# power_7V.net
KiCad netlist of a schematic drawn in Altium Designer
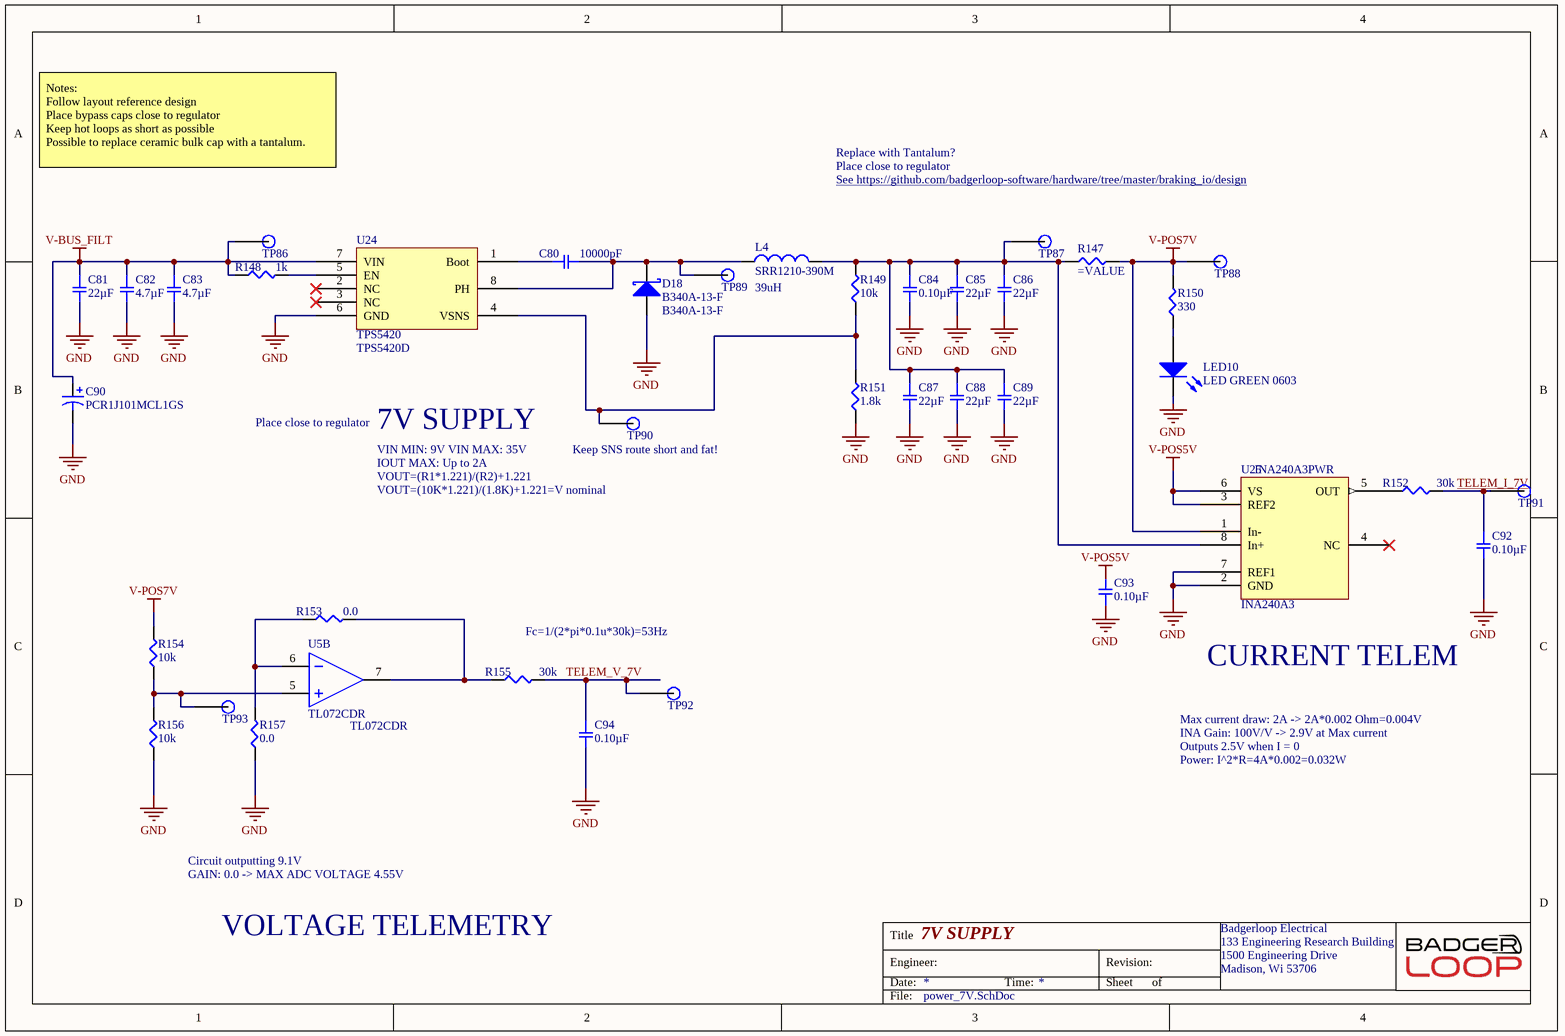
[diagram p0: power_7V.SchDoc]

(export (version "E")
  (design (tool "Eeschema 10.0.6"))
  (components
    (comp (ref "C80")
      (value "10000pF")
      (footprint "SMD-0805C")
      (description "CAP CER 10000PF 250V X7T 0805")
      (fields
        (field (name "DIGI-KEY PART NUMBER") "490-13986-1-ND")
        (field (name "PART NUMBER") "GC321AD72E103KX01D")
      )
      (libsource (lib "capacitors") (part "GC321AD72E103KX01D"))
    )
    (comp (ref "C81")
      (value "22µF")
      (footprint "SMD-1206C")
      (description "CAP CER 22UF 25V X5R 1206")
      (fields
        (field (name "DIGI-KEY PART NUMBER") "490-12451-1-ND")
        (field (name "PART NUMBER") "GRT31CR61E226ME01L")
      )
      (libsource (lib "capacitors") (part "GRT31CR61E226ME01L"))
    )
    (comp (ref "C82")
      (value "4.7µF")
      (footprint "SMD-1206C")
      (description "CAP CER 4.7UF 50V X7S 1206")
      (fields
        (field (name "DIGI-KEY PART NUMBER") "490-11167-1-ND")
        (field (name "PART NUMBER") "GCM31CC71H475KA03L")
      )
      (libsource (lib "capacitors") (part "GCM31CC71H475KA03L"))
    )
    (comp (ref "C83")
      (value "4.7µF")
      (footprint "SMD-1206C")
      (description "CAP CER 4.7UF 50V X7S 1206")
      (fields
        (field (name "DIGI-KEY PART NUMBER") "490-11167-1-ND")
        (field (name "PART NUMBER") "GCM31CC71H475KA03L")
      )
      (libsource (lib "capacitors") (part "GCM31CC71H475KA03L"))
    )
    (comp (ref "C84")
      (value "0.10µF")
      (footprint "SMD-0805C")
      (description "CAP CER 0.1UF 10V U2J 0805")
      (fields
        (field (name "DIGI-KEY PART NUMBER") "490-11592-1-ND")
        (field (name "PART NUMBER") "GRM21B7U1A104JA01L")
      )
      (libsource (lib "capacitors") (part "GRM21B7U1A104JA01L"))
    )
    (comp (ref "C85")
      (value "22µF")
      (footprint "SMD-1206C")
      (description "CAP CER 22UF 25V X5R 1206")
      (fields
        (field (name "DIGI-KEY PART NUMBER") "490-12451-1-ND")
        (field (name "PART NUMBER") "GRT31CR61E226ME01L")
      )
      (libsource (lib "capacitors") (part "GRT31CR61E226ME01L"))
    )
    (comp (ref "C86")
      (value "22µF")
      (footprint "SMD-1206C")
      (description "CAP CER 22UF 25V X5R 1206")
      (fields
        (field (name "DIGI-KEY PART NUMBER") "490-12451-1-ND")
        (field (name "PART NUMBER") "GRT31CR61E226ME01L")
      )
      (libsource (lib "capacitors") (part "GRT31CR61E226ME01L"))
    )
    (comp (ref "C87")
      (value "22µF")
      (footprint "SMD-1206C")
      (description "CAP CER 22UF 25V X5R 1206")
      (fields
        (field (name "DIGI-KEY PART NUMBER") "490-12451-1-ND")
        (field (name "PART NUMBER") "GRT31CR61E226ME01L")
      )
      (libsource (lib "capacitors") (part "GRT31CR61E226ME01L"))
    )
    (comp (ref "C88")
      (value "22µF")
      (footprint "SMD-1206C")
      (description "CAP CER 22UF 25V X5R 1206")
      (fields
        (field (name "DIGI-KEY PART NUMBER") "490-12451-1-ND")
        (field (name "PART NUMBER") "GRT31CR61E226ME01L")
      )
      (libsource (lib "capacitors") (part "GRT31CR61E226ME01L"))
    )
    (comp (ref "C89")
      (value "22µF")
      (footprint "SMD-1206C")
      (description "CAP CER 22UF 25V X5R 1206")
      (fields
        (field (name "DIGI-KEY PART NUMBER") "490-12451-1-ND")
        (field (name "PART NUMBER") "GRT31CR61E226ME01L")
      )
      (libsource (lib "capacitors") (part "GRT31CR61E226ME01L"))
    )
    (comp (ref "C90")
      (value "PCR1J101MCL1GS")
      (footprint "CAPAE110103X126M")
      (description "CAP ALUM POLY 100UF 20% 63V SMD")
      (fields (field (name "MANUFACTURER") "Nichicon") (field (name "TOLERANCE") "20%"))
      (libsource (lib "capacitors") (part "PCR1J101MCL1GS"))
    )
    (comp (ref "C92")
      (value "0.10µF")
      (footprint "SMD-0805C")
      (description "CAP CER 0.1UF 16V X7R 0805")
      (fields
        (field (name "DIGI-KEY PART NUMBER") "490-1683-1-ND")
        (field (name "PART NUMBER") "GRM219R71C104KA01D")
      )
      (libsource (lib "capacitors") (part "GRM219R71C104KA01D"))
    )
    (comp (ref "C93")
      (value "0.10µF")
      (footprint "SMD-0805C")
      (description "CAP CER 0.1UF 10V U2J 0805")
      (fields
        (field (name "DIGI-KEY PART NUMBER") "490-11592-1-ND")
        (field (name "PART NUMBER") "GRM21B7U1A104JA01L")
      )
      (libsource (lib "capacitors") (part "GRM21B7U1A104JA01L"))
    )
    (comp (ref "C94")
      (value "0.10µF")
      (footprint "SMD-0805C")
      (description "CAP CER 0.1UF 16V X7R 0805")
      (fields
        (field (name "DIGI-KEY PART NUMBER") "490-1683-1-ND")
        (field (name "PART NUMBER") "GRM219R71C104KA01D")
      )
      (libsource (lib "capacitors") (part "GRM219R71C104KA01D"))
    )
    (comp (ref "D18")
      (value "B340A-13-F")
      (footprint "DIOM4326X20N")
      (description "DIODE SCHOTTKY 40V 3A SMA")
      (fields
        (field (name "MANUFACTURER") "Diodes")
        (field (name "VOLTAGE") "40V")
        (field (name "MANUFACTURER PART NUMBER") "B340A-13-F")
      )
      (libsource (lib "misc") (part "B340A-13-F"))
    )
    (comp (ref "L4")
      (value "SRR1210-390M")
      (footprint "INDM120120X100N")
      (description "FIXED IND 39UH 4.2A 66 MOHM SMD")
      (fields
        (field (name "MANUFACTURER") "Bourns")
        (field (name "TOLERANCE") "20%")
        (field (name "INDUCTANCE") "39uH")
      )
      (libsource (lib "inductor") (part "SRR1210-390M"))
    )
    (comp (ref "LED10")
      (value "LED GREEN 0603")
      (footprint "LED 0603 GREEN")
      (fields (field (name "MANUFACTURER") "Lite-On Inc."))
      (libsource (lib "misc") (part "LED GREEN 0603"))
    )
    (comp (ref "R147")
      (value "~")
      (footprint "SMD-1206-RES")
      (description "RES SMD 0.002 OHM 1% 1W 1206")
      (fields
        (field (name "MANUFACTURER") "Stackpole Electronics")
        (field (name "MANUFACTURER PART NUMBER") "CSNL1206FT2L00")
      )
      (libsource (lib "resistors") (part "CSNL1206FT2L00TR"))
    )
    (comp (ref "R148")
      (value "1k")
      (footprint "SMD-0805-RES")
      (description "RES SMD 1K OHM 5% 1/2W 0805")
      (fields
        (field (name "PART NUMBER") "ERJ-P06J102V")
        (field (name "DIGI-KEY PART NUMBER") "P1.0KADCT-ND")
      )
      (libsource (lib "resistors") (part "ERJ-P06J102V"))
    )
    (comp (ref "R149")
      (value "10k")
      (footprint "SMD-0805-RES")
      (description "RES SMD 10K OHM 5% 1/2W 0805")
      (fields (field (name "PART NUMBER") "ERJ-P06J103V") (field (name "DIGI-KEY PART NUMBER") "P10KADCT-ND"))
      (libsource (lib "resistors") (part "ERJ-P06J103V"))
    )
    (comp (ref "R150")
      (value "330")
      (footprint "SMD-0805-RES")
      (description "RES SMD 330 OHM 5% 1/2W 0805")
      (fields (field (name "PART NUMBER") "ERJ-P06J331V") (field (name "DIGI-KEY PART NUMBER") "P330ADCT-ND"))
      (libsource (lib "resistors") (part "ERJ-P06J331V"))
    )
    (comp (ref "R151")
      (value "1.8k")
      (footprint "SMD-0805-RES")
      (description "RES SMD 1.8K OHM 1% 1/2W 0805")
      (fields
        (field (name "PART NUMBER") "ERJ-P6WF1801V")
        (field (name "DIGI-KEY PART NUMBER") "P16888CT-ND")
      )
      (libsource (lib "resistors") (part "ERJ-P6WF1801V"))
    )
    (comp (ref "R152")
      (value "30k")
      (footprint "SMD-0805-RES")
      (description "RES SMD 30K OHM 1% 1/8W 0805")
      (fields
        (field (name "PART NUMBER") "ERJ-6ENF3002V")
        (field (name "DIGI-KEY PART NUMBER") "P30.0KCCT-ND")
      )
      (libsource (lib "resistors") (part "ERJ-6ENF3002V"))
    )
    (comp (ref "R153")
      (value "0.0")
      (footprint "SMD-0805-RES")
      (description "RES SMD 0.0 OHM JUMPER 1/8W 0805")
      (fields (field (name "PART NUMBER") "ERJ-6GEY0R00V") (field (name "DIGI-KEY PART NUMBER") "P0.0ACT-ND"))
      (libsource (lib "resistors") (part "ERJ-6GEY0R00V"))
    )
    (comp (ref "R154")
      (value "10k")
      (footprint "SMD-0805-RES")
      (description "RES SMD 10K OHM 5% 1/2W 0805")
      (fields (field (name "PART NUMBER") "ERJ-P06J103V") (field (name "DIGI-KEY PART NUMBER") "P10KADCT-ND"))
      (libsource (lib "resistors") (part "ERJ-P06J103V"))
    )
    (comp (ref "R155")
      (value "30k")
      (footprint "SMD-0805-RES")
      (description "RES SMD 30K OHM 1% 1/8W 0805")
      (fields
        (field (name "PART NUMBER") "ERJ-6ENF3002V")
        (field (name "DIGI-KEY PART NUMBER") "P30.0KCCT-ND")
      )
      (libsource (lib "resistors") (part "ERJ-6ENF3002V"))
    )
    (comp (ref "R156")
      (value "10k")
      (footprint "SMD-0805-RES")
      (description "RES SMD 10K OHM 5% 1/2W 0805")
      (fields (field (name "PART NUMBER") "ERJ-P06J103V") (field (name "DIGI-KEY PART NUMBER") "P10KADCT-ND"))
      (libsource (lib "resistors") (part "ERJ-P06J103V"))
    )
    (comp (ref "R157")
      (value "0.0")
      (footprint "SMD-0805-RES")
      (description "RES SMD 0.0 OHM JUMPER 1/8W 0805")
      (fields (field (name "PART NUMBER") "ERJ-6GEY0R00V") (field (name "DIGI-KEY PART NUMBER") "P0.0ACT-ND"))
      (libsource (lib "resistors") (part "ERJ-6GEY0R00V"))
    )
    (comp (ref "TP86")
      (value "TP")
      (footprint "Test Point")
      (description "SMD TEST POINT")
      (libsource (lib "misc") (part "TP"))
    )
    (comp (ref "TP87")
      (value "TP")
      (footprint "Test Point")
      (description "SMD TEST POINT")
      (libsource (lib "misc") (part "TP"))
    )
    (comp (ref "TP88")
      (value "TP")
      (footprint "Test Point")
      (description "SMD TEST POINT")
      (libsource (lib "misc") (part "TP"))
    )
    (comp (ref "TP89")
      (value "TP")
      (footprint "Test Point")
      (description "SMD TEST POINT")
      (libsource (lib "misc") (part "TP"))
    )
    (comp (ref "TP90")
      (value "TP")
      (footprint "Test Point")
      (description "SMD TEST POINT")
      (libsource (lib "misc") (part "TP"))
    )
    (comp (ref "TP91")
      (value "TP")
      (footprint "Test Point")
      (description "SMD TEST POINT")
      (libsource (lib "misc") (part "TP"))
    )
    (comp (ref "TP92")
      (value "TP")
      (footprint "Test Point")
      (description "SMD TEST POINT")
      (libsource (lib "misc") (part "TP"))
    )
    (comp (ref "TP93")
      (value "TP")
      (footprint "Test Point")
      (description "SMD TEST POINT")
      (libsource (lib "misc") (part "TP"))
    )
    (comp (ref "U5")
      (value "TL072CDR")
      (footprint "SOP127P600X175-8N")
      (description "IC OPAMP JFET 3MHZ 8SOIC")
      (fields
        (field (name "MANUFACTURER") "Texas Instruments")
        (field (name "MANUFACTURER PART NUMBER") "TL072CDR")
      )
      (libsource (lib "ic") (part "TL072CDR"))
    )
    (comp (ref "U24")
      (value "TPS5420")
      (footprint "SOP127P600X175-8N")
      (description "5.5V to 36V Input, 2A, 500kHz Step-Down Converter")
      (fields
        (field (name "MANUFACTURER") "Texas Instruments")
        (field (name "MANUFACTURER PART NUMBER") "TPS5420D")
      )
      (libsource (lib "ic") (part "TPS5420"))
    )
    (comp (ref "U25")
      (value "INA240A3")
      (footprint "SOIC127P600X175-8N")
      (description "IC AMP CURRENT SENSE 8-TSSOP 100V/V")
      (fields
        (field (name "MANUFACTURER") "Texas Instruments")
        (field (name "MANUFACTURER PART NUMBER") "INA240A3PWR")
      )
      (libsource (lib "ic") (part "INA240A3"))
    )
  )
  (nets
    (net (code "1") (name "/TELEM_I_7V") (class "Default")
      (node (ref "C92") (pin "1") (pinfunction "1_1") (pintype "passive"))
      (node (ref "R152") (pin "2") (pinfunction "2_2") (pintype "passive"))
      (node (ref "TP91") (pin "1") (pinfunction "1_1") (pintype "passive"))
    )
    (net (code "2") (name "/TELEM_V_7V") (class "Default")
      (node (ref "C94") (pin "1") (pinfunction "1_1") (pintype "passive"))
      (node (ref "R155") (pin "2") (pinfunction "2_2") (pintype "passive"))
      (node (ref "TP92") (pin "1") (pinfunction "1_1") (pintype "passive"))
    )
    (net (code "3") (name "GND") (class "Default")
      (node (ref "C81") (pin "2") (pinfunction "2_2") (pintype "passive"))
      (node (ref "C82") (pin "2") (pinfunction "2_2") (pintype "passive"))
      (node (ref "C83") (pin "2") (pinfunction "2_2") (pintype "passive"))
      (node (ref "C84") (pin "2") (pinfunction "2_2") (pintype "passive"))
      (node (ref "C85") (pin "2") (pinfunction "2_2") (pintype "passive"))
      (node (ref "C86") (pin "2") (pinfunction "2_2") (pintype "passive"))
      (node (ref "C87") (pin "2") (pinfunction "2_2") (pintype "passive"))
      (node (ref "C88") (pin "2") (pinfunction "2_2") (pintype "passive"))
      (node (ref "C89") (pin "2") (pinfunction "2_2") (pintype "passive"))
      (node (ref "C90") (pin "2") (pinfunction "2_2") (pintype "passive"))
      (node (ref "C92") (pin "2") (pinfunction "2_2") (pintype "passive"))
      (node (ref "C93") (pin "1") (pinfunction "1_1") (pintype "passive"))
      (node (ref "C94") (pin "2") (pinfunction "2_2") (pintype "passive"))
      (node (ref "D18") (pin "1") (pinfunction "A_1") (pintype "passive"))
      (node (ref "LED10") (pin "2") (pinfunction "K_2") (pintype "passive"))
      (node (ref "R151") (pin "1") (pinfunction "1_1") (pintype "passive"))
      (node (ref "R156") (pin "1") (pinfunction "1_1") (pintype "passive"))
      (node (ref "R157") (pin "1") (pinfunction "1_1") (pintype "passive"))
      (node (ref "U24") (pin "6") (pinfunction "GND_6") (pintype "passive"))
      (node (ref "U25") (pin "2") (pinfunction "GND_2") (pintype "power_in"))
      (node (ref "U25") (pin "7") (pinfunction "REF1_7") (pintype "passive"))
    )
    (net (code "4") (name "Net-(D18-K)") (class "Default")
      (node (ref "C80") (pin "2") (pinfunction "2_2") (pintype "passive"))
      (node (ref "D18") (pin "2") (pinfunction "K_2") (pintype "passive"))
      (node (ref "L4") (pin "1") (pinfunction "1_1") (pintype "passive"))
      (node (ref "TP89") (pin "1") (pinfunction "1_1") (pintype "passive"))
      (node (ref "U24") (pin "8") (pinfunction "PH_8") (pintype "passive"))
    )
    (net (code "5") (name "Net-(LED10-A)") (class "Default")
      (node (ref "LED10") (pin "1") (pinfunction "A_1") (pintype "passive"))
      (node (ref "R150") (pin "1") (pinfunction "1_1") (pintype "passive"))
    )
    (net (code "6") (name "Net-(U5B-IN+)") (class "Default")
      (node (ref "R154") (pin "1") (pinfunction "1_1") (pintype "passive"))
      (node (ref "R156") (pin "2") (pinfunction "2_2") (pintype "passive"))
      (node (ref "TP93") (pin "1") (pinfunction "1_1") (pintype "passive"))
      (node (ref "U5") (pin "5") (pinfunction "IN+_5") (pintype "passive"))
    )
    (net (code "7") (name "Net-(U5B-IN-)") (class "Default")
      (node (ref "R153") (pin "1") (pinfunction "1_1") (pintype "passive"))
      (node (ref "R157") (pin "2") (pinfunction "2_2") (pintype "passive"))
      (node (ref "U5") (pin "6") (pinfunction "IN-_6") (pintype "passive"))
    )
    (net (code "8") (name "Net-(U5B-OUT)") (class "Default")
      (node (ref "R153") (pin "2") (pinfunction "2_2") (pintype "passive"))
      (node (ref "R155") (pin "1") (pinfunction "1_1") (pintype "passive"))
      (node (ref "U5") (pin "7") (pinfunction "OUT_7") (pintype "passive"))
    )
    (net (code "9") (name "Net-(U24-Boot)") (class "Default")
      (node (ref "C80") (pin "1") (pinfunction "1_1") (pintype "passive"))
      (node (ref "U24") (pin "1") (pinfunction "Boot_1") (pintype "passive"))
    )
    (net (code "10") (name "Net-(U24-EN)") (class "Default")
      (node (ref "R148") (pin "2") (pinfunction "2_2") (pintype "passive"))
      (node (ref "U24") (pin "5") (pinfunction "EN_5") (pintype "passive"))
    )
    (net (code "11") (name "Net-(U24-VSNS)") (class "Default")
      (node (ref "R149") (pin "1") (pinfunction "1_1") (pintype "passive"))
      (node (ref "R151") (pin "2") (pinfunction "2_2") (pintype "passive"))
      (node (ref "TP90") (pin "1") (pinfunction "1_1") (pintype "passive"))
      (node (ref "U24") (pin "4") (pinfunction "VSNS_4") (pintype "power_in"))
    )
    (net (code "12") (name "Net-(U25-In+)") (class "Default")
      (node (ref "C84") (pin "1") (pinfunction "1_1") (pintype "passive"))
      (node (ref "C85") (pin "1") (pinfunction "1_1") (pintype "passive"))
      (node (ref "C86") (pin "1") (pinfunction "1_1") (pintype "passive"))
      (node (ref "C87") (pin "1") (pinfunction "1_1") (pintype "passive"))
      (node (ref "C88") (pin "1") (pinfunction "1_1") (pintype "passive"))
      (node (ref "C89") (pin "1") (pinfunction "1_1") (pintype "passive"))
      (node (ref "L4") (pin "2") (pinfunction "2_2") (pintype "passive"))
      (node (ref "R147") (pin "1") (pinfunction "1_1") (pintype "passive"))
      (node (ref "R149") (pin "2") (pinfunction "2_2") (pintype "passive"))
      (node (ref "TP87") (pin "1") (pinfunction "1_1") (pintype "passive"))
      (node (ref "U25") (pin "8") (pinfunction "In+_8") (pintype "passive"))
    )
    (net (code "13") (name "Net-(U25-OUT)") (class "Default")
      (node (ref "R152") (pin "1") (pinfunction "1_1") (pintype "passive"))
      (node (ref "U25") (pin "5") (pinfunction "OUT_5") (pintype "output"))
    )
    (net (code "14") (name "V-BUS_FILT") (class "Default")
      (node (ref "C81") (pin "1") (pinfunction "1_1") (pintype "passive"))
      (node (ref "C82") (pin "1") (pinfunction "1_1") (pintype "passive"))
      (node (ref "C83") (pin "1") (pinfunction "1_1") (pintype "passive"))
      (node (ref "C90") (pin "1") (pinfunction "1_1") (pintype "passive"))
      (node (ref "R148") (pin "1") (pinfunction "1_1") (pintype "passive"))
      (node (ref "TP86") (pin "1") (pinfunction "1_1") (pintype "passive"))
      (node (ref "U24") (pin "7") (pinfunction "VIN_7") (pintype "passive"))
    )
    (net (code "15") (name "V-POS5V") (class "Default")
      (node (ref "C93") (pin "2") (pinfunction "2_2") (pintype "passive"))
      (node (ref "U25") (pin "3") (pinfunction "REF2_3") (pintype "passive"))
      (node (ref "U25") (pin "6") (pinfunction "VS_6") (pintype "power_in"))
    )
    (net (code "16") (name "V-POS7V") (class "Default")
      (node (ref "R147") (pin "2") (pinfunction "2_2") (pintype "passive"))
      (node (ref "R150") (pin "2") (pinfunction "2_2") (pintype "passive"))
      (node (ref "R154") (pin "2") (pinfunction "2_2") (pintype "passive"))
      (node (ref "TP88") (pin "1") (pinfunction "1_1") (pintype "passive"))
      (node (ref "U25") (pin "1") (pinfunction "In-_1") (pintype "passive"))
    )
    (net (code "17") (name "unconnected-(U24-NC-Pad2)") (class "Default")
      (node (ref "U24") (pin "2") (pinfunction "NC_2") (pintype "power_in+no_connect"))
    )
    (net (code "18") (name "unconnected-(U24-NC-Pad3)") (class "Default")
      (node (ref "U24") (pin "3") (pinfunction "NC_3") (pintype "passive+no_connect"))
    )
    (net (code "19") (name "unconnected-(U25-NC-Pad4)") (class "Default")
      (node (ref "U25") (pin "4") (pinfunction "NC_4") (pintype "passive+no_connect"))
    )
  )
)
